# mechanical.net
KiCad netlist of a schematic drawn in Altium Designer
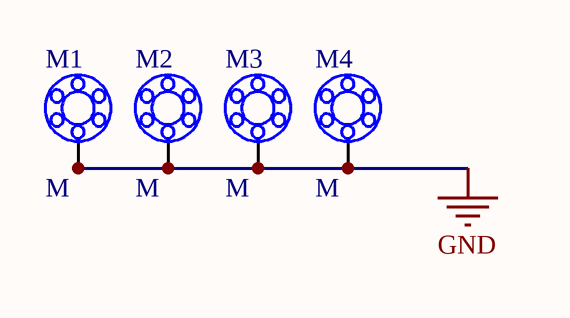
[diagram p0: mechanical.SchDoc]

(export (version "E")
  (design (tool "Eeschema 10.0.6"))
  (components
    (comp (ref "M1")
      (value "M")
      (footprint "MOUNTING")
      (description "MOUNTING HOLE - NON INSTALLABLE")
      (libsource (lib "vh_altium_library") (part "MOUNTING"))
    )
    (comp (ref "M2")
      (value "M")
      (footprint "MOUNTING")
      (description "MOUNTING HOLE - NON INSTALLABLE")
      (libsource (lib "vh_altium_library") (part "MOUNTING"))
    )
    (comp (ref "M3")
      (value "M")
      (footprint "MOUNTING")
      (description "MOUNTING HOLE - NON INSTALLABLE")
      (libsource (lib "vh_altium_library") (part "MOUNTING"))
    )
    (comp (ref "M4")
      (value "M")
      (footprint "MOUNTING")
      (description "MOUNTING HOLE - NON INSTALLABLE")
      (libsource (lib "vh_altium_library") (part "MOUNTING"))
    )
  )
  (nets
    (net (code "1") (name "GND") (class "Default")
      (node (ref "M1") (pin "1") (pinfunction "1_1") (pintype "passive"))
      (node (ref "M1") (pin "2") (pinfunction "2_2") (pintype "passive"))
      (node (ref "M1") (pin "3") (pinfunction "3_3") (pintype "passive"))
      (node (ref "M1") (pin "4") (pinfunction "4_4") (pintype "passive"))
      (node (ref "M1") (pin "5") (pinfunction "5_5") (pintype "passive"))
      (node (ref "M1") (pin "6") (pinfunction "6_6") (pintype "passive"))
      (node (ref "M1") (pin "7") (pinfunction "7_7") (pintype "passive"))
      (node (ref "M2") (pin "1") (pinfunction "1_1") (pintype "passive"))
      (node (ref "M2") (pin "2") (pinfunction "2_2") (pintype "passive"))
      (node (ref "M2") (pin "3") (pinfunction "3_3") (pintype "passive"))
      (node (ref "M2") (pin "4") (pinfunction "4_4") (pintype "passive"))
      (node (ref "M2") (pin "5") (pinfunction "5_5") (pintype "passive"))
      (node (ref "M2") (pin "6") (pinfunction "6_6") (pintype "passive"))
      (node (ref "M2") (pin "7") (pinfunction "7_7") (pintype "passive"))
      (node (ref "M3") (pin "1") (pinfunction "1_1") (pintype "passive"))
      (node (ref "M3") (pin "2") (pinfunction "2_2") (pintype "passive"))
      (node (ref "M3") (pin "3") (pinfunction "3_3") (pintype "passive"))
      (node (ref "M3") (pin "4") (pinfunction "4_4") (pintype "passive"))
      (node (ref "M3") (pin "5") (pinfunction "5_5") (pintype "passive"))
      (node (ref "M3") (pin "6") (pinfunction "6_6") (pintype "passive"))
      (node (ref "M3") (pin "7") (pinfunction "7_7") (pintype "passive"))
      (node (ref "M4") (pin "1") (pinfunction "1_1") (pintype "passive"))
      (node (ref "M4") (pin "2") (pinfunction "2_2") (pintype "passive"))
      (node (ref "M4") (pin "3") (pinfunction "3_3") (pintype "passive"))
      (node (ref "M4") (pin "4") (pinfunction "4_4") (pintype "passive"))
      (node (ref "M4") (pin "5") (pinfunction "5_5") (pintype "passive"))
      (node (ref "M4") (pin "6") (pinfunction "6_6") (pintype "passive"))
      (node (ref "M4") (pin "7") (pinfunction "7_7") (pintype "passive"))
    )
  )
)
